# MCU.net
KiCad netlist of a schematic drawn in Altium Designer
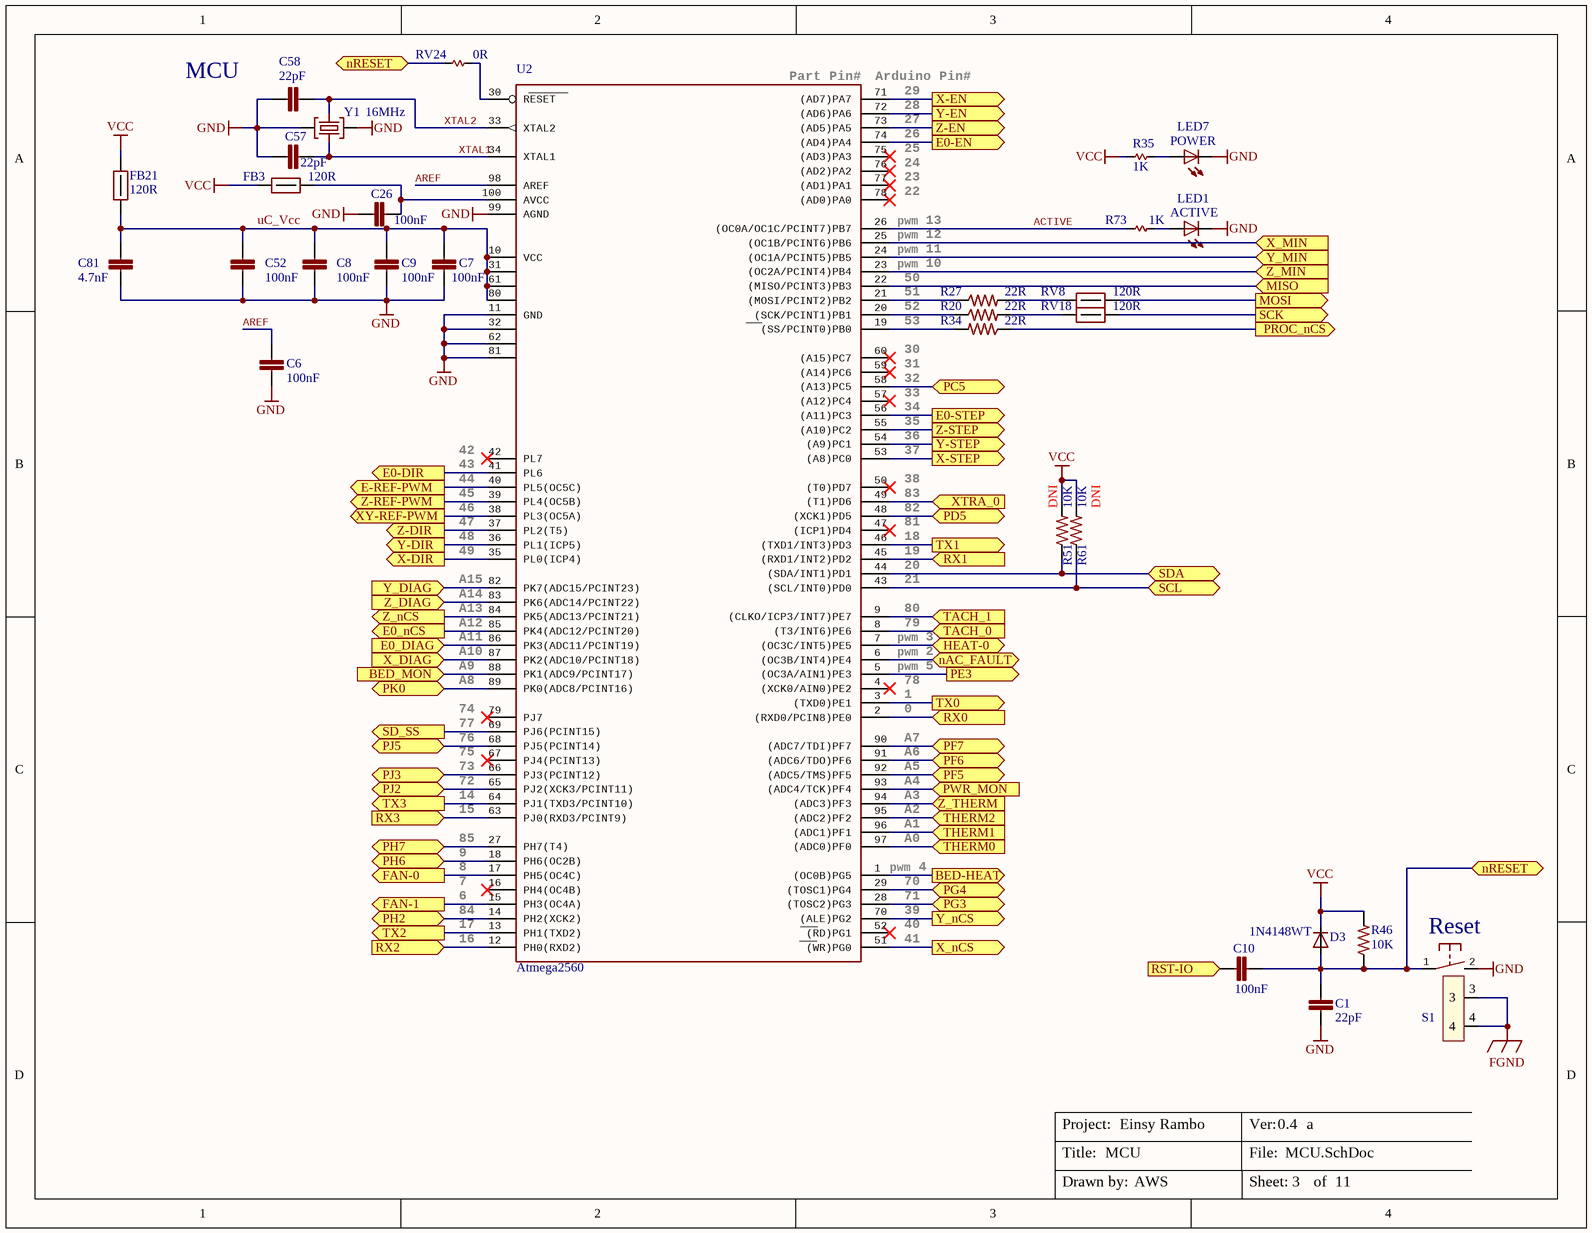
[diagram p0: MCU.SchDoc]

(export (version "E")
  (design (tool "Eeschema 10.0.6"))
  (components
    (comp (ref "C1")
      (value "22pF")
      (footprint "C0402")
      (description "CAP CER 0402 22pF 50V 5% C0G")
      (fields (field (name "MANUFACTURER") "AVX") (field (name "PART") "22pF 50V"))
      (libsource (lib "3Delight") (part "04025A220JAT2A"))
    )
    (comp (ref "C6")
      (value "100nF")
      (footprint "C0402")
      (description "CAP CER 0402 100nF 16V 10% X7R")
      (fields (field (name "MANUFACTURER") "Murata") (field (name "TOLERANCE") "+/- 10%"))
      (libsource (lib "3Delight") (part "GRM155R71C104KA88D"))
    )
    (comp (ref "C7")
      (value "100nF")
      (footprint "C0402")
      (description "CAP CER 0402 100nF 16V 10% X7R")
      (fields (field (name "MANUFACTURER") "Murata") (field (name "TOLERANCE") "+/- 10%"))
      (libsource (lib "3Delight") (part "GRM155R71C104KA88D"))
    )
    (comp (ref "C8")
      (value "100nF")
      (footprint "C0402")
      (description "CAP CER 0402 100nF 16V 10% X7R")
      (fields (field (name "MANUFACTURER") "Murata") (field (name "TOLERANCE") "+/- 10%"))
      (libsource (lib "3Delight") (part "GRM155R71C104KA88D"))
    )
    (comp (ref "C9")
      (value "100nF")
      (footprint "C0402")
      (description "CAP CER 0402 100nF 16V 10% X7R")
      (fields (field (name "MANUFACTURER") "Murata") (field (name "TOLERANCE") "+/- 10%"))
      (libsource (lib "3Delight") (part "GRM155R71C104KA88D"))
    )
    (comp (ref "C10")
      (value "100nF")
      (footprint "C0402")
      (description "CAP CER 0402 100nF 16V 10% X7R")
      (fields (field (name "MANUFACTURER") "Murata") (field (name "TOLERANCE") "+/- 10%"))
      (libsource (lib "") (part "GRM155R71C104KA88D_1"))
    )
    (comp (ref "C26")
      (value "100nF")
      (footprint "C0402")
      (description "CAP CER 0402 100nF 16V 10% X7R")
      (fields (field (name "MANUFACTURER") "Murata") (field (name "TOLERANCE") "+/- 10%"))
      (libsource (lib "") (part "GRM155R71C104KA88D_2"))
    )
    (comp (ref "C52")
      (value "100nF")
      (footprint "C0402")
      (description "CAP CER 0402 100nF 16V 10% X7R")
      (fields (field (name "MANUFACTURER") "Murata") (field (name "TOLERANCE") "+/- 10%"))
      (libsource (lib "3Delight") (part "GRM155R71C104KA88D"))
    )
    (comp (ref "C57")
      (value "22pF")
      (footprint "C0402")
      (description "CAP CER 0402 22pF 50V 5% C0G")
      (fields (field (name "MANUFACTURER") "AVX") (field (name "PART") "22pF 50V"))
      (libsource (lib "") (part "04025A220JAT2A_1"))
    )
    (comp (ref "C58")
      (value "22pF")
      (footprint "C0402")
      (description "CAP CER 0402 22pF 50V 5% C0G")
      (fields (field (name "MANUFACTURER") "AVX") (field (name "PART") "22pF 50V"))
      (libsource (lib "") (part "04025A220JAT2A_1"))
    )
    (comp (ref "C81")
      (value "4.7nF")
      (footprint "C0402")
      (description "CAP CER 0402 4.7nF 25V 10% X7R")
      (fields (field (name "MANUFACTURER") "YAGEO") (field (name "TOLERANCE") "+/- 10%"))
      (libsource (lib "3Delight") (part "CC0402KRX7R8BB472"))
    )
    (comp (ref "D3")
      (value "1N4148WT")
      (footprint "SOD523")
      (description "DIODE SOD523")
      (fields (field (name "MANUFACTURER") "Fairchild") (field (name "TOLERANCE") "NA"))
      (libsource (lib "3Delight") (part "1N4148WT"))
    )
    (comp (ref "FB3")
      (value "120R")
      (footprint "FB0603")
      (description "FERRITE BEAD 120 OHM 0603 1LN")
      (fields (field (name "MANUFACTURER") "Samsung") (field (name "PART") "FERRITE 120R 3A 0603"))
      (libsource (lib "3Delight") (part "FERRITE 220R 2.5A 0603"))
    )
    (comp (ref "FB21")
      (value "120R")
      (footprint "FB0603")
      (description "FERRITE BEAD 120 OHM 0603 1LN")
      (fields (field (name "MANUFACTURER") "Samsung") (field (name "PART") "FERRITE 120R 3A 0603"))
      (libsource (lib "Inductors") (part "FERRITE 120R 3A 0603"))
    )
    (comp (ref "LED1")
      (value "YEL")
      (footprint "LED2012120")
      (description "LED 0805 Yellow")
      (fields (field (name "MANUFACTURER") "Dialight") (field (name "TOLERANCE") "NA"))
      (libsource (lib "3Delight") (part "5988140107F"))
    )
    (comp (ref "LED7")
      (value "GRN")
      (footprint "LED2012120")
      (description "LED 0805 Green")
      (fields (field (name "MANUFACTURER") "Dialight") (field (name "TOLERANCE") "NA"))
      (libsource (lib "3Delight") (part "5988170107F"))
    )
    (comp (ref "R20")
      (value "22R")
      (footprint "R0402")
      (description "RES 0402 22r 62.5mW 1%")
      (fields (field (name "MANUFACTURER") "Yageo") (field (name "TOLERANCE") "+/- 1%"))
      (libsource (lib "3Delight") (part "RC0402FR-0722RL"))
    )
    (comp (ref "R27")
      (value "22R")
      (footprint "R0402")
      (description "RES 0402 22r 62.5mW 1%")
      (fields (field (name "MANUFACTURER") "Yageo") (field (name "TOLERANCE") "+/- 1%"))
      (libsource (lib "3Delight") (part "RC0402FR-0722RL"))
    )
    (comp (ref "R34")
      (value "22R")
      (footprint "R0402")
      (description "RES 0402 22r 62.5mW 1%")
      (fields (field (name "MANUFACTURER") "Yageo") (field (name "TOLERANCE") "+/- 1%"))
      (libsource (lib "3Delight") (part "RC0402FR-0722RL"))
    )
    (comp (ref "R35")
      (value "1K")
      (footprint "R0402")
      (description "RES SMD 1K OHM 1% 1/16W 0402")
      (fields (field (name "MANUFACTURER") "Yageo") (field (name "PART") "1k"))
      (libsource (lib "3Delight") (part "RC0402FR-071KL"))
    )
    (comp (ref "R46")
      (value "10K")
      (footprint "R0402")
      (description "RES SMD 10K OHM 1% 1/16W 0402")
      (fields (field (name "MANUFACTURER") "Yageo") (field (name "PART") "10k 1% 0402"))
      (libsource (lib "3Delight") (part "RC0402FR-0710KP"))
    )
    (comp (ref "R51")
      (value "10K")
      (footprint "R0402")
      (description "RES SMD 10K OHM 1% 1/16W 0402")
      (fields
        (field (name "MANUFACTURER") "Yageo")
        (field (name "PART") "10k 1% 0402")
        (field (name "DNI") "DNI")
      )
      (libsource (lib "3Delight") (part "RC0402FR-0710KP"))
    )
    (comp (ref "R61")
      (value "10K")
      (footprint "R0402")
      (description "RES SMD 10K OHM 1% 1/16W 0402")
      (fields
        (field (name "MANUFACTURER") "Yageo")
        (field (name "PART") "10k 1% 0402")
        (field (name "DNI") "DNI")
      )
      (libsource (lib "3Delight") (part "RC0402FR-0710KP"))
    )
    (comp (ref "R73")
      (value "1K")
      (footprint "R0402")
      (description "RES SMD 1K OHM 1% 1/16W 0402")
      (fields (field (name "MANUFACTURER") "Yageo") (field (name "PART") "1k"))
      (libsource (lib "3Delight") (part "RC0402FR-071KL"))
    )
    (comp (ref "RV8")
      (value "120R")
      (footprint "R0402")
      (description "FERRITE BEAD 120 OHM 0402 1LN")
      (fields (field (name "MANUFACTURER") "Taiyo Yuden") (field (name "PART") "FERRITE 120R 1A 0402"))
      (libsource (lib "Inductors") (part "FERRITE 120R 1A 0402"))
    )
    (comp (ref "RV18")
      (value "120R")
      (footprint "R0402")
      (description "FERRITE BEAD 120 OHM 0402 1LN")
      (fields (field (name "MANUFACTURER") "Taiyo Yuden") (field (name "PART") "FERRITE 120R 1A 0402"))
      (libsource (lib "Inductors") (part "FERRITE 120R 1A 0402"))
    )
    (comp (ref "RV24")
      (value "0R")
      (footprint "R0402")
      (description "RES SMD 0.0OHM JUMPER 1/10W 0402")
      (fields (field (name "MANUFACTURER") "Panasonic") (field (name "TOLERANCE") "1%"))
      (libsource (lib "Resistors") (part "0R 0402"))
    )
    (comp (ref "S1")
      (value "1571610-2")
      (footprint "B3F-31XX")
      (description "SWTCH Momentary Washable")
      (fields (field (name "MANUFACTURER") "TE") (field (name "PART") "Tact PB R/A"))
      (libsource (lib "3Delight") (part "1571610-2"))
    )
    (comp (ref "U2")
      (value "Atmega2560")
      (footprint "TSQFP50P1600X1600X120-100L")
      (fields
        (field (name "MANUFACTURER") "Microchip")
        (field (name "PART") "ATMEGA2560")
        (field (name "TOLERANCE") "NA")
      )
      (libsource (lib "ICs-uC") (part "ATMEGA2560AU_SM"))
    )
    (comp (ref "Y1")
      (value "16MHz")
      (footprint "CRYS320250")
      (description "Crystal 16mHz 10ppm 10pF")
      (fields (field (name "MANUFACTURER") "TXC") (field (name "TOLERANCE") "10ppm"))
      (libsource (lib "3Delight") (part "7M-16.000MEEQ-T"))
    )
  )
  (nets
    (net (code "1") (name "/ACTIVE") (class "Default")
      (node (ref "R73") (pin "2") (pinfunction "2_2") (pintype "passive"))
      (node (ref "U2") (pin "26") (pinfunction "(OC0A/OC1C/PCINT7)PB7_26") (pintype "passive"))
    )
    (net (code "2") (name "/AREF") (class "Default")
      (node (ref "C6") (pin "1") (pinfunction "1_1") (pintype "passive"))
      (node (ref "U2") (pin "98") (pinfunction "AREF_98") (pintype "passive"))
    )
    (net (code "3") (name "/BED-HEAT") (class "Default")
      (node (ref "U2") (pin "1") (pinfunction "(OC0B)PG5_1") (pintype "passive"))
    )
    (net (code "4") (name "/BED_MON") (class "Default")
      (node (ref "U2") (pin "88") (pinfunction "PK1(ADC9/PCINT17)_88") (pintype "passive"))
    )
    (net (code "5") (name "/E-REF-PWM") (class "Default")
      (node (ref "U2") (pin "40") (pinfunction "PL5(OC5C)_40") (pintype "passive"))
    )
    (net (code "6") (name "/E0-DIR") (class "Default")
      (node (ref "U2") (pin "41") (pinfunction "PL6_41") (pintype "passive"))
    )
    (net (code "7") (name "/E0-EN") (class "Default")
      (node (ref "U2") (pin "74") (pinfunction "(AD4)PA4_74") (pintype "passive"))
    )
    (net (code "8") (name "/E0-STEP") (class "Default")
      (node (ref "U2") (pin "56") (pinfunction "(A11)PC3_56") (pintype "passive"))
    )
    (net (code "9") (name "/E0_DIAG") (class "Default")
      (node (ref "U2") (pin "86") (pinfunction "PK3(ADC11/PCINT19)_86") (pintype "passive"))
    )
    (net (code "10") (name "/E0_nCS") (class "Default")
      (node (ref "U2") (pin "85") (pinfunction "PK4(ADC12/PCINT20)_85") (pintype "passive"))
    )
    (net (code "11") (name "/FAN-0") (class "Default")
      (node (ref "U2") (pin "17") (pinfunction "PH5(OC4C)_17") (pintype "passive"))
    )
    (net (code "12") (name "/FAN-1") (class "Default")
      (node (ref "U2") (pin "15") (pinfunction "PH3(OC4A)_15") (pintype "passive"))
    )
    (net (code "13") (name "/HEAT-0") (class "Default")
      (node (ref "U2") (pin "7") (pinfunction "(OC3C/INT5)PE5_7") (pintype "passive"))
    )
    (net (code "14") (name "/MISO") (class "Default")
      (node (ref "U2") (pin "22") (pinfunction "(MISO/PCINT3)PB3_22") (pintype "passive"))
    )
    (net (code "15") (name "/MOSI") (class "Default")
      (node (ref "RV8") (pin "2") (pinfunction "2_2") (pintype "passive"))
    )
    (net (code "16") (name "/PC5") (class "Default")
      (node (ref "U2") (pin "58") (pinfunction "(A13)PC5_58") (pintype "passive"))
    )
    (net (code "17") (name "/PD5") (class "Default")
      (node (ref "U2") (pin "48") (pinfunction "(XCK1)PD5_48") (pintype "passive"))
    )
    (net (code "18") (name "/PE3") (class "Default")
      (node (ref "U2") (pin "5") (pinfunction "(OC3A/AIN1)PE3_5") (pintype "passive"))
    )
    (net (code "19") (name "/PF5") (class "Default")
      (node (ref "U2") (pin "92") (pinfunction "(ADC5/TMS)PF5_92") (pintype "passive"))
    )
    (net (code "20") (name "/PF6") (class "Default")
      (node (ref "U2") (pin "91") (pinfunction "(ADC6/TDO)PF6_91") (pintype "passive"))
    )
    (net (code "21") (name "/PF7") (class "Default")
      (node (ref "U2") (pin "90") (pinfunction "(ADC7/TDI)PF7_90") (pintype "passive"))
    )
    (net (code "22") (name "/PG3") (class "Default")
      (node (ref "U2") (pin "28") (pinfunction "(TOSC2)PG3_28") (pintype "passive"))
    )
    (net (code "23") (name "/PG4") (class "Default")
      (node (ref "U2") (pin "29") (pinfunction "(TOSC1)PG4_29") (pintype "passive"))
    )
    (net (code "24") (name "/PH2") (class "Default")
      (node (ref "U2") (pin "14") (pinfunction "PH2(XCK2)_14") (pintype "passive"))
    )
    (net (code "25") (name "/PH6") (class "Default")
      (node (ref "U2") (pin "18") (pinfunction "PH6(OC2B)_18") (pintype "passive"))
    )
    (net (code "26") (name "/PH7") (class "Default")
      (node (ref "U2") (pin "27") (pinfunction "PH7(T4)_27") (pintype "passive"))
    )
    (net (code "27") (name "/PJ2") (class "Default")
      (node (ref "U2") (pin "65") (pinfunction "PJ2(XCK3/PCINT11)_65") (pintype "passive"))
    )
    (net (code "28") (name "/PJ3") (class "Default")
      (node (ref "U2") (pin "66") (pinfunction "PJ3(PCINT12)_66") (pintype "passive"))
    )
    (net (code "29") (name "/PJ5") (class "Default")
      (node (ref "U2") (pin "68") (pinfunction "PJ5(PCINT14)_68") (pintype "passive"))
    )
    (net (code "30") (name "/PK0") (class "Default")
      (node (ref "U2") (pin "89") (pinfunction "PK0(ADC8/PCINT16)_89") (pintype "passive"))
    )
    (net (code "31") (name "/PROC_nCS") (class "Default")
      (node (ref "R34") (pin "1") (pinfunction "1_1") (pintype "passive"))
    )
    (net (code "32") (name "/PWR_MON") (class "Default")
      (node (ref "U2") (pin "93") (pinfunction "(ADC4/TCK)PF4_93") (pintype "passive"))
    )
    (net (code "33") (name "/RST-IO") (class "Default")
      (node (ref "C10") (pin "1") (pinfunction "1_1") (pintype "passive"))
    )
    (net (code "34") (name "/RX0") (class "Default")
      (node (ref "U2") (pin "2") (pinfunction "(RXD0/PCIN8)PE0_2") (pintype "passive"))
    )
    (net (code "35") (name "/RX1") (class "Default")
      (node (ref "U2") (pin "45") (pinfunction "(RXD1/INT2)PD2_45") (pintype "passive"))
    )
    (net (code "36") (name "/RX2") (class "Default")
      (node (ref "U2") (pin "12") (pinfunction "PH0(RXD2)_12") (pintype "passive"))
    )
    (net (code "37") (name "/RX3") (class "Default")
      (node (ref "U2") (pin "63") (pinfunction "PJ0(RXD3/PCINT9)_63") (pintype "passive"))
    )
    (net (code "38") (name "/SCK") (class "Default")
      (node (ref "RV18") (pin "2") (pinfunction "2_2") (pintype "passive"))
    )
    (net (code "39") (name "/SCL") (class "Default")
      (node (ref "R61") (pin "1") (pinfunction "1_1") (pintype "passive"))
      (node (ref "U2") (pin "43") (pinfunction "(SCL/INT0)PD0_43") (pintype "passive"))
    )
    (net (code "40") (name "/SDA") (class "Default")
      (node (ref "R51") (pin "1") (pinfunction "1_1") (pintype "passive"))
      (node (ref "U2") (pin "44") (pinfunction "(SDA/INT1)PD1_44") (pintype "passive"))
    )
    (net (code "41") (name "/SD_SS") (class "Default")
      (node (ref "U2") (pin "69") (pinfunction "PJ6(PCINT15)_69") (pintype "passive"))
    )
    (net (code "42") (name "/TACH_0") (class "Default")
      (node (ref "U2") (pin "8") (pinfunction "(T3/INT6)PE6_8") (pintype "passive"))
    )
    (net (code "43") (name "/TACH_1") (class "Default")
      (node (ref "U2") (pin "9") (pinfunction "(CLKO/ICP3/INT7)PE7_9") (pintype "passive"))
    )
    (net (code "44") (name "/THERM0") (class "Default")
      (node (ref "U2") (pin "97") (pinfunction "(ADC0)PF0_97") (pintype "passive"))
    )
    (net (code "45") (name "/THERM1") (class "Default")
      (node (ref "U2") (pin "96") (pinfunction "(ADC1)PF1_96") (pintype "passive"))
    )
    (net (code "46") (name "/THERM2") (class "Default")
      (node (ref "U2") (pin "95") (pinfunction "(ADC2)PF2_95") (pintype "passive"))
    )
    (net (code "47") (name "/TX0") (class "Default")
      (node (ref "U2") (pin "3") (pinfunction "(TXD0)PE1_3") (pintype "passive"))
    )
    (net (code "48") (name "/TX1") (class "Default")
      (node (ref "U2") (pin "46") (pinfunction "(TXD1/INT3)PD3_46") (pintype "passive"))
    )
    (net (code "49") (name "/TX2") (class "Default")
      (node (ref "U2") (pin "13") (pinfunction "PH1(TXD2)_13") (pintype "passive"))
    )
    (net (code "50") (name "/TX3") (class "Default")
      (node (ref "U2") (pin "64") (pinfunction "PJ1(TXD3/PCINT10)_64") (pintype "passive"))
    )
    (net (code "51") (name "/X-DIR") (class "Default")
      (node (ref "U2") (pin "35") (pinfunction "PL0(ICP4)_35") (pintype "passive"))
    )
    (net (code "52") (name "/X-EN") (class "Default")
      (node (ref "U2") (pin "71") (pinfunction "(AD7)PA7_71") (pintype "passive"))
    )
    (net (code "53") (name "/X-STEP") (class "Default")
      (node (ref "U2") (pin "53") (pinfunction "(A8)PC0_53") (pintype "passive"))
    )
    (net (code "54") (name "/XTAL1") (class "Default")
      (node (ref "C57") (pin "1") (pinfunction "1_1") (pintype "passive"))
      (node (ref "U2") (pin "34") (pinfunction "XTAL1_34") (pintype "passive"))
      (node (ref "Y1") (pin "1") (pinfunction "C1_1") (pintype "passive"))
    )
    (net (code "55") (name "/XTAL2") (class "Default")
      (node (ref "C58") (pin "1") (pinfunction "1_1") (pintype "passive"))
      (node (ref "U2") (pin "33") (pinfunction "XTAL2_33") (pintype "output"))
      (node (ref "Y1") (pin "3") (pinfunction "C2_3") (pintype "passive"))
    )
    (net (code "56") (name "/XTRA_0") (class "Default")
      (node (ref "U2") (pin "49") (pinfunction "(T1)PD6_49") (pintype "passive"))
    )
    (net (code "57") (name "/XY-REF-PWM") (class "Default")
      (node (ref "U2") (pin "38") (pinfunction "PL3(OC5A)_38") (pintype "passive"))
    )
    (net (code "58") (name "/X_DIAG") (class "Default")
      (node (ref "U2") (pin "87") (pinfunction "PK2(ADC10/PCINT18)_87") (pintype "passive"))
    )
    (net (code "59") (name "/X_MIN") (class "Default")
      (node (ref "U2") (pin "25") (pinfunction "(OC1B/PCINT6)PB6_25") (pintype "passive"))
    )
    (net (code "60") (name "/X_nCS") (class "Default")
      (node (ref "U2") (pin "51") (pinfunction "(WR)PG0_51") (pintype "passive"))
    )
    (net (code "61") (name "/Y-DIR") (class "Default")
      (node (ref "U2") (pin "36") (pinfunction "PL1(ICP5)_36") (pintype "passive"))
    )
    (net (code "62") (name "/Y-EN") (class "Default")
      (node (ref "U2") (pin "72") (pinfunction "(AD6)PA6_72") (pintype "passive"))
    )
    (net (code "63") (name "/Y-STEP") (class "Default")
      (node (ref "U2") (pin "54") (pinfunction "(A9)PC1_54") (pintype "passive"))
    )
    (net (code "64") (name "/Y_DIAG") (class "Default")
      (node (ref "U2") (pin "82") (pinfunction "PK7(ADC15/PCINT23)_82") (pintype "passive"))
    )
    (net (code "65") (name "/Y_MIN") (class "Default")
      (node (ref "U2") (pin "24") (pinfunction "(OC1A/PCINT5)PB5_24") (pintype "passive"))
    )
    (net (code "66") (name "/Y_nCS") (class "Default")
      (node (ref "U2") (pin "70") (pinfunction "(ALE)PG2_70") (pintype "passive"))
    )
    (net (code "67") (name "/Z-DIR") (class "Default")
      (node (ref "U2") (pin "37") (pinfunction "PL2(T5)_37") (pintype "passive"))
    )
    (net (code "68") (name "/Z-EN") (class "Default")
      (node (ref "U2") (pin "73") (pinfunction "(AD5)PA5_73") (pintype "passive"))
    )
    (net (code "69") (name "/Z-REF-PWM") (class "Default")
      (node (ref "U2") (pin "39") (pinfunction "PL4(OC5B)_39") (pintype "passive"))
    )
    (net (code "70") (name "/Z-STEP") (class "Default")
      (node (ref "U2") (pin "55") (pinfunction "(A10)PC2_55") (pintype "passive"))
    )
    (net (code "71") (name "/Z_DIAG") (class "Default")
      (node (ref "U2") (pin "83") (pinfunction "PK6(ADC14/PCINT22)_83") (pintype "passive"))
    )
    (net (code "72") (name "/Z_MIN") (class "Default")
      (node (ref "U2") (pin "23") (pinfunction "(OC2A/PCINT4)PB4_23") (pintype "passive"))
    )
    (net (code "73") (name "/Z_THERM") (class "Default")
      (node (ref "U2") (pin "94") (pinfunction "(ADC3)PF3_94") (pintype "passive"))
    )
    (net (code "74") (name "/Z_nCS") (class "Default")
      (node (ref "U2") (pin "84") (pinfunction "PK5(ADC13/PCINT21)_84") (pintype "passive"))
    )
    (net (code "75") (name "/nAC_FAULT") (class "Default")
      (node (ref "U2") (pin "6") (pinfunction "(OC3B/INT4)PE4_6") (pintype "passive"))
    )
    (net (code "76") (name "/nRESET") (class "Default")
      (node (ref "C1") (pin "1") (pinfunction "1_1") (pintype "passive"))
      (node (ref "C10") (pin "2") (pinfunction "2_2") (pintype "passive"))
      (node (ref "D3") (pin "A") (pinfunction "A_A") (pintype "passive"))
      (node (ref "R46") (pin "1") (pinfunction "1_1") (pintype "passive"))
      (node (ref "RV24") (pin "1") (pinfunction "1_1") (pintype "passive"))
      (node (ref "S1") (pin "1") (pinfunction "P_1") (pintype "passive"))
    )
    (net (code "77") (name "/uC_Vcc") (class "Default")
      (node (ref "C52") (pin "1") (pinfunction "1_1") (pintype "passive"))
      (node (ref "C7") (pin "1") (pinfunction "1_1") (pintype "passive"))
      (node (ref "C8") (pin "1") (pinfunction "1_1") (pintype "passive"))
      (node (ref "C81") (pin "1") (pinfunction "1_1") (pintype "passive"))
      (node (ref "C9") (pin "1") (pinfunction "1_1") (pintype "passive"))
      (node (ref "FB21") (pin "2") (pinfunction "2_2") (pintype "passive"))
      (node (ref "U2") (pin "10") (pinfunction "VCC_10") (pintype "power_in"))
      (node (ref "U2") (pin "31") (pinfunction "VCC1_31") (pintype "power_in"))
      (node (ref "U2") (pin "61") (pinfunction "VCC2_61") (pintype "power_in"))
      (node (ref "U2") (pin "80") (pinfunction "VCC3_80") (pintype "power_in"))
    )
    (net (code "78") (name "FGND") (class "Default")
      (node (ref "S1") (pin "3") (pinfunction "3_3") (pintype "power_in"))
      (node (ref "S1") (pin "4") (pinfunction "4_4") (pintype "power_in"))
    )
    (net (code "79") (name "GND") (class "Default")
      (node (ref "C1") (pin "2") (pinfunction "2_2") (pintype "passive"))
      (node (ref "C26") (pin "2") (pinfunction "2_2") (pintype "passive"))
      (node (ref "C52") (pin "2") (pinfunction "2_2") (pintype "passive"))
      (node (ref "C57") (pin "2") (pinfunction "2_2") (pintype "passive"))
      (node (ref "C58") (pin "2") (pinfunction "2_2") (pintype "passive"))
      (node (ref "C6") (pin "2") (pinfunction "2_2") (pintype "passive"))
      (node (ref "C7") (pin "2") (pinfunction "2_2") (pintype "passive"))
      (node (ref "C8") (pin "2") (pinfunction "2_2") (pintype "passive"))
      (node (ref "C81") (pin "2") (pinfunction "2_2") (pintype "passive"))
      (node (ref "C9") (pin "2") (pinfunction "2_2") (pintype "passive"))
      (node (ref "LED1") (pin "C") (pinfunction "C_C") (pintype "passive"))
      (node (ref "LED7") (pin "C") (pinfunction "C_C") (pintype "passive"))
      (node (ref "S1") (pin "2") (pinfunction "S_2") (pintype "passive"))
      (node (ref "U2") (pin "11") (pinfunction "GND_11") (pintype "power_in"))
      (node (ref "U2") (pin "32") (pinfunction "GND1_32") (pintype "power_in"))
      (node (ref "U2") (pin "62") (pinfunction "GND2_62") (pintype "power_in"))
      (node (ref "U2") (pin "81") (pinfunction "GND3_81") (pintype "power_in"))
      (node (ref "U2") (pin "99") (pinfunction "AGND_99") (pintype "power_in"))
      (node (ref "Y1") (pin "2") (pinfunction "GND_2") (pintype "passive"))
      (node (ref "Y1") (pin "4") (pinfunction "GND_4") (pintype "passive"))
    )
    (net (code "80") (name "Net-(LED1-PadA)") (class "Default")
      (node (ref "LED1") (pin "A") (pinfunction "A_A") (pintype "passive"))
      (node (ref "R73") (pin "1") (pinfunction "1_1") (pintype "passive"))
    )
    (net (code "81") (name "Net-(LED7-PadA)") (class "Default")
      (node (ref "LED7") (pin "A") (pinfunction "A_A") (pintype "passive"))
      (node (ref "R35") (pin "1") (pinfunction "1_1") (pintype "passive"))
    )
    (net (code "82") (name "Net-(R20-Pad2)") (class "Default")
      (node (ref "R20") (pin "2") (pinfunction "2_2") (pintype "passive"))
      (node (ref "RV18") (pin "1") (pinfunction "1_1") (pintype "passive"))
    )
    (net (code "83") (name "Net-(R27-Pad2)") (class "Default")
      (node (ref "R27") (pin "2") (pinfunction "2_2") (pintype "passive"))
      (node (ref "RV8") (pin "1") (pinfunction "1_1") (pintype "passive"))
    )
    (net (code "84") (name "Net-(U2-(MOSI{slash}PCINT2)PB2)") (class "Default")
      (node (ref "R27") (pin "1") (pinfunction "1_1") (pintype "passive"))
      (node (ref "U2") (pin "21") (pinfunction "(MOSI/PCINT2)PB2_21") (pintype "passive"))
    )
    (net (code "85") (name "Net-(U2-(SCK{slash}PCINT1)PB1)") (class "Default")
      (node (ref "R20") (pin "1") (pinfunction "1_1") (pintype "passive"))
      (node (ref "U2") (pin "20") (pinfunction "(SCK/PCINT1)PB1_20") (pintype "passive"))
    )
    (net (code "86") (name "Net-(U2-(SS{slash}PCINT0)PB0)") (class "Default")
      (node (ref "R34") (pin "2") (pinfunction "2_2") (pintype "passive"))
      (node (ref "U2") (pin "19") (pinfunction "(SS/PCINT0)PB0_19") (pintype "passive"))
    )
    (net (code "87") (name "Net-(U2-AVCC)") (class "Default")
      (node (ref "C26") (pin "1") (pinfunction "1_1") (pintype "passive"))
      (node (ref "FB3") (pin "2") (pinfunction "2_2") (pintype "passive"))
      (node (ref "U2") (pin "100") (pinfunction "AVCC_100") (pintype "power_in"))
    )
    (net (code "88") (name "Net-(U2-RESET)") (class "Default")
      (node (ref "RV24") (pin "2") (pinfunction "2_2") (pintype "passive"))
      (node (ref "U2") (pin "30") (pinfunction "RESET_30") (pintype "passive"))
    )
    (net (code "89") (name "VCC") (class "Default")
      (node (ref "D3") (pin "C") (pinfunction "C_C") (pintype "passive"))
      (node (ref "FB21") (pin "1") (pinfunction "1_1") (pintype "passive"))
      (node (ref "FB3") (pin "1") (pinfunction "1_1") (pintype "passive"))
      (node (ref "R35") (pin "2") (pinfunction "2_2") (pintype "passive"))
      (node (ref "R46") (pin "2") (pinfunction "2_2") (pintype "passive"))
      (node (ref "R51") (pin "2") (pinfunction "2_2") (pintype "passive"))
      (node (ref "R61") (pin "2") (pinfunction "2_2") (pintype "passive"))
    )
    (net (code "90") (name "unconnected-(U2-(A12)PC4-Pad57)") (class "Default")
      (node (ref "U2") (pin "57") (pinfunction "(A12)PC4_57") (pintype "passive+no_connect"))
    )
    (net (code "91") (name "unconnected-(U2-(A14)PC6-Pad59)") (class "Default")
      (node (ref "U2") (pin "59") (pinfunction "(A14)PC6_59") (pintype "passive+no_connect"))
    )
    (net (code "92") (name "unconnected-(U2-(A15)PC7-Pad60)") (class "Default")
      (node (ref "U2") (pin "60") (pinfunction "(A15)PC7_60") (pintype "passive+no_connect"))
    )
    (net (code "93") (name "unconnected-(U2-(AD0)PA0-Pad78)") (class "Default")
      (node (ref "U2") (pin "78") (pinfunction "(AD0)PA0_78") (pintype "passive+no_connect"))
    )
    (net (code "94") (name "unconnected-(U2-(AD1)PA1-Pad77)") (class "Default")
      (node (ref "U2") (pin "77") (pinfunction "(AD1)PA1_77") (pintype "passive+no_connect"))
    )
    (net (code "95") (name "unconnected-(U2-(AD2)PA2-Pad76)") (class "Default")
      (node (ref "U2") (pin "76") (pinfunction "(AD2)PA2_76") (pintype "passive+no_connect"))
    )
    (net (code "96") (name "unconnected-(U2-(AD3)PA3-Pad75)") (class "Default")
      (node (ref "U2") (pin "75") (pinfunction "(AD3)PA3_75") (pintype "passive+no_connect"))
    )
    (net (code "97") (name "unconnected-(U2-(ICP1)PD4-Pad47)") (class "Default")
      (node (ref "U2") (pin "47") (pinfunction "(ICP1)PD4_47") (pintype "passive+no_connect"))
    )
    (net (code "98") (name "unconnected-(U2-(RD)PG1-Pad52)") (class "Default")
      (node (ref "U2") (pin "52") (pinfunction "(RD)PG1_52") (pintype "passive+no_connect"))
    )
    (net (code "99") (name "unconnected-(U2-(T0)PD7-Pad50)") (class "Default")
      (node (ref "U2") (pin "50") (pinfunction "(T0)PD7_50") (pintype "passive+no_connect"))
    )
    (net (code "100") (name "unconnected-(U2-(XCK0{slash}AIN0)PE2-Pad4)") (class "Default")
      (node (ref "U2") (pin "4") (pinfunction "(XCK0/AIN0)PE2_4") (pintype "passive+no_connect"))
    )
    (net (code "101") (name "unconnected-(U2-PH4(OC4B)-Pad16)") (class "Default")
      (node (ref "U2") (pin "16") (pinfunction "PH4(OC4B)_16") (pintype "passive+no_connect"))
    )
    (net (code "102") (name "unconnected-(U2-PJ4(PCINT13)-Pad67)") (class "Default")
      (node (ref "U2") (pin "67") (pinfunction "PJ4(PCINT13)_67") (pintype "passive+no_connect"))
    )
    (net (code "103") (name "unconnected-(U2-PJ7-Pad79)") (class "Default")
      (node (ref "U2") (pin "79") (pinfunction "PJ7_79") (pintype "passive+no_connect"))
    )
    (net (code "104") (name "unconnected-(U2-PL7-Pad42)") (class "Default")
      (node (ref "U2") (pin "42") (pinfunction "PL7_42") (pintype "passive+no_connect"))
    )
  )
)
